# ESP_Robo_Board.net
KiCad netlist of a schematic drawn in EAGLE
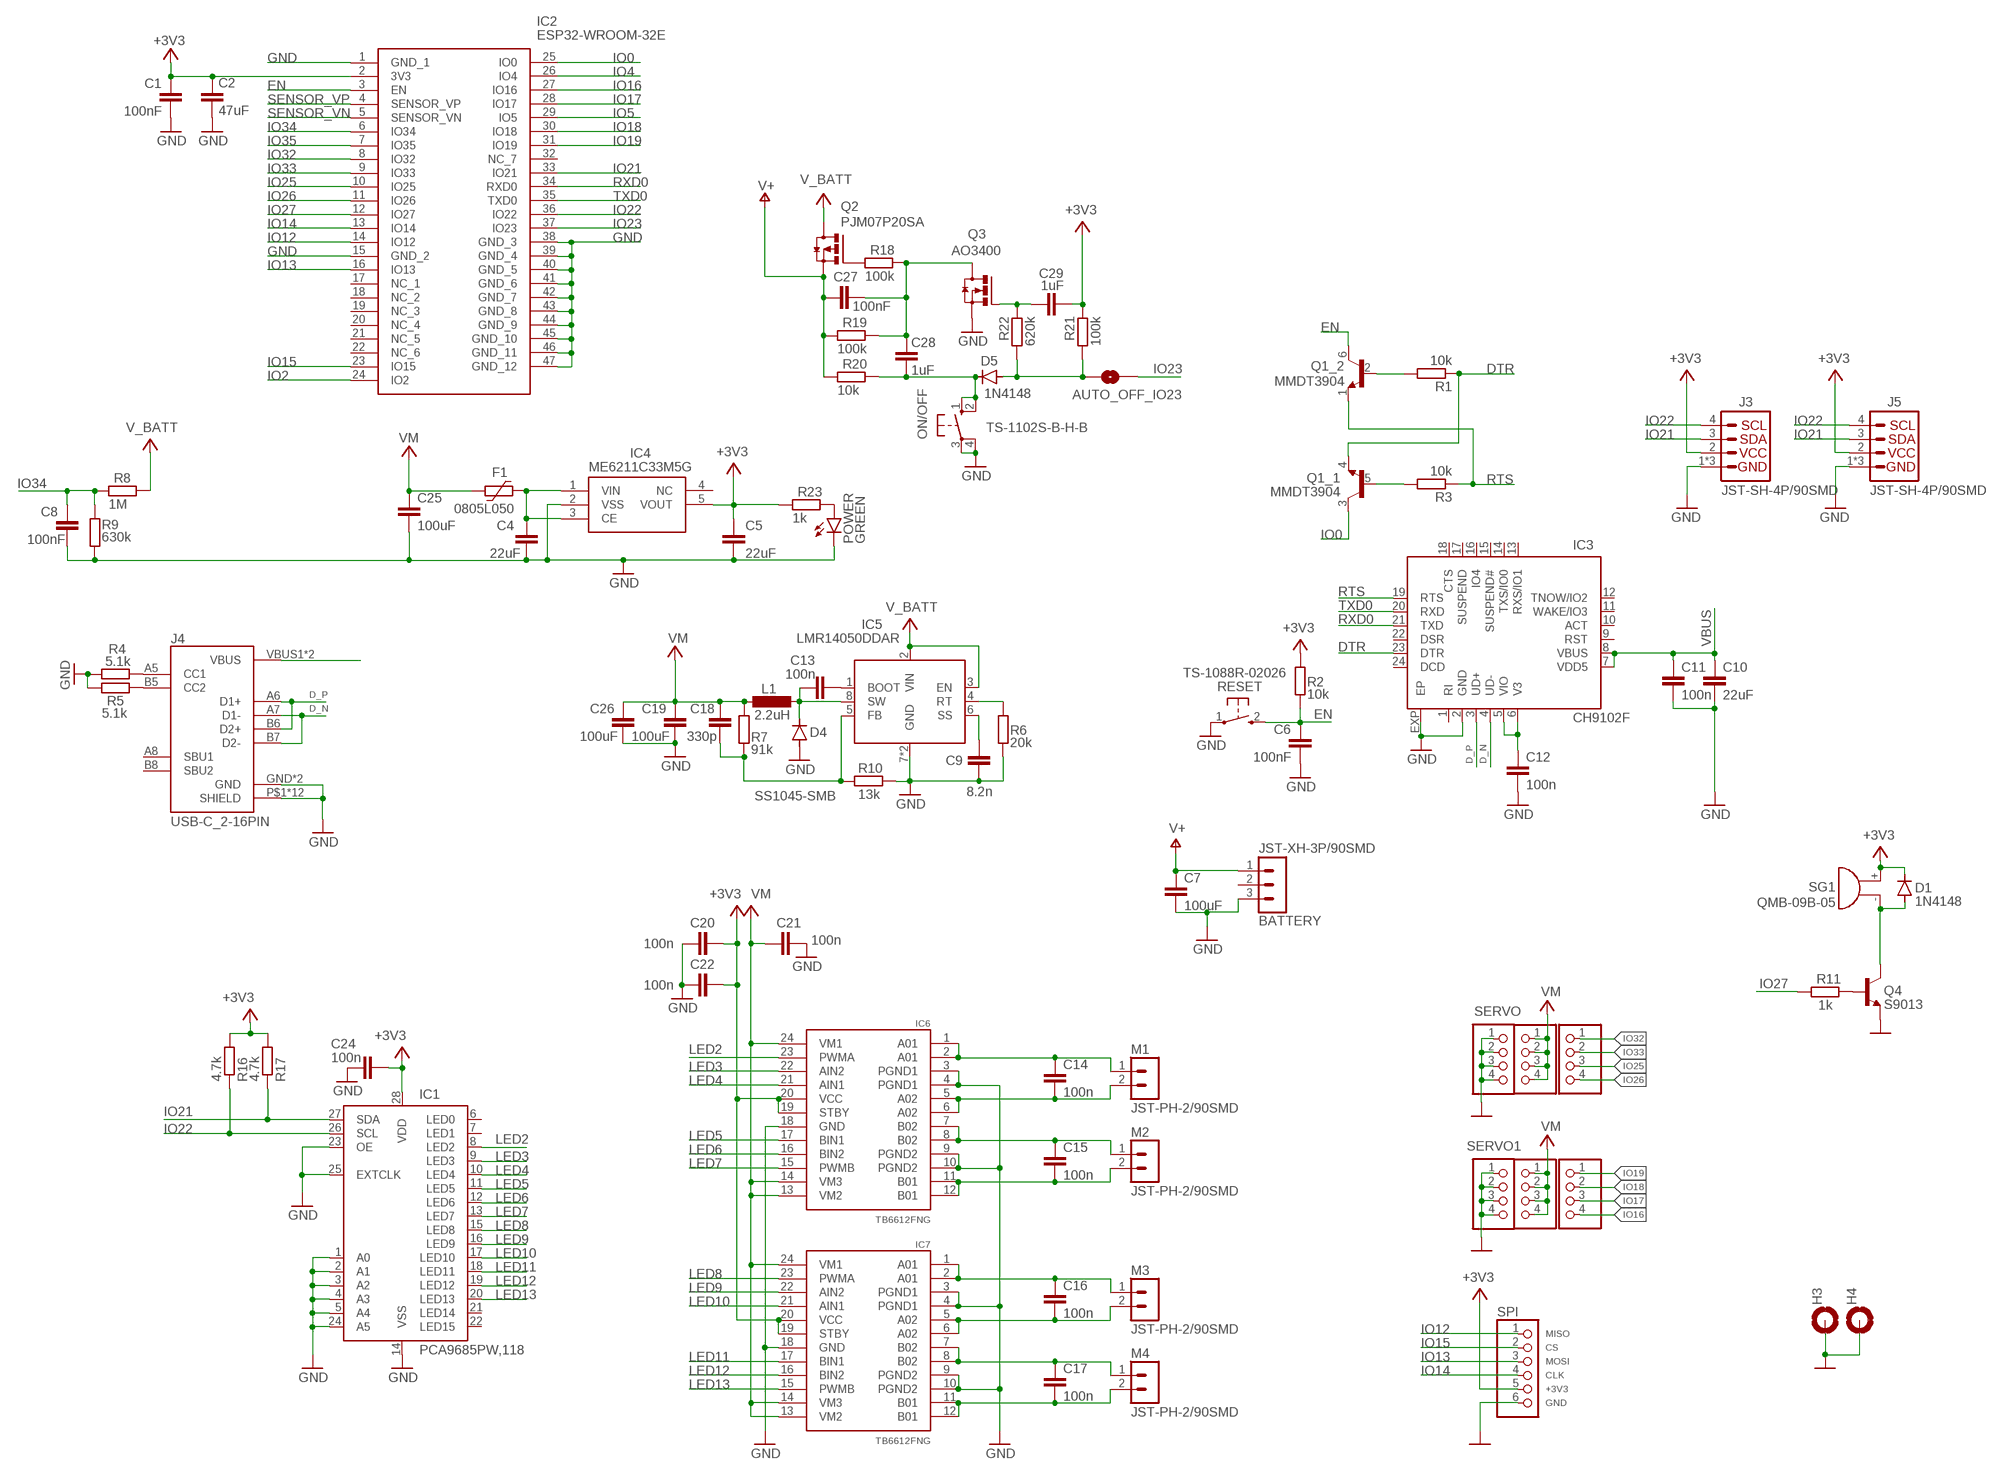
[diagram p0: schematic, sheet 1]

(export (version "E")
  (design (tool "Eeschema 10.0.6"))
  (components
    (comp (ref "1")
      (value "PINHD_1X4_RED")
      (footprint "eagle-import:1X04")
      (libsource (lib "eagle-import") (part "PINHD-1X4"))
    )
    (comp (ref "2")
      (value "PINHD_1X4_BLACK")
      (footprint "eagle-import:1X04")
      (libsource (lib "eagle-import") (part "PINHD-1X4"))
    )
    (comp (ref "5")
      (value "PINHD_1X4_RED")
      (footprint "eagle-import:1X04")
      (libsource (lib "eagle-import") (part "PINHD-1X4"))
    )
    (comp (ref "6")
      (value "PINHD_1X4_BLACK")
      (footprint "eagle-import:1X04")
      (libsource (lib "eagle-import") (part "PINHD-1X4"))
    )
    (comp (ref "AUTO_OFF_IO23")
      (value "nv")
      (footprint "eagle-import:SMT-JUMPER_2_NO_SILK")
      (libsource (lib "eagle-import") (part "JUMPER-SMT_2_NO_SILK"))
    )
    (comp (ref "BATTERY")
      (value "JST-XH-3P/90SMD")
      (footprint "eagle-import:S3B-XH-SM4")
      (libsource (lib "eagle-import") (part "JST-XH-3/90SMD"))
    )
    (comp (ref "C1")
      (value "100nF")
      (footprint "eagle-import:C0603")
      (libsource (lib "eagle-import") (part "C-EUC0603"))
    )
    (comp (ref "C2")
      (value "47uF")
      (footprint "eagle-import:C0805")
      (libsource (lib "eagle-import") (part "C-EUC0805"))
    )
    (comp (ref "C4")
      (value "22uF")
      (footprint "eagle-import:C0603")
      (libsource (lib "eagle-import") (part "C-EUC0603"))
    )
    (comp (ref "C5")
      (value "22uF")
      (footprint "eagle-import:C0603")
      (fields (field (name "LCSC_PART") "C19666"))
      (libsource (lib "eagle-import") (part "C-EUC0603"))
    )
    (comp (ref "C6")
      (value "100nF")
      (footprint "eagle-import:C0402")
      (libsource (lib "eagle-import") (part "CAPACITOR_0402"))
    )
    (comp (ref "C7")
      (value "100uF")
      (footprint "eagle-import:C1206")
      (libsource (lib "eagle-import") (part "C-EUC1206"))
    )
    (comp (ref "C8")
      (value "100nF")
      (footprint "eagle-import:C0402")
      (libsource (lib "eagle-import") (part "CAPACITOR_0402"))
    )
    (comp (ref "C9")
      (value "8.2n")
      (footprint "eagle-import:C0603")
      (libsource (lib "eagle-import") (part "C-EUC0603"))
    )
    (comp (ref "C10")
      (value "22uF")
      (footprint "eagle-import:C0603")
      (libsource (lib "eagle-import") (part "C-EUC0603"))
    )
    (comp (ref "C11")
      (value "100n")
      (footprint "eagle-import:C0402")
      (libsource (lib "eagle-import") (part "CAPACITOR_0402"))
    )
    (comp (ref "C12")
      (value "100n")
      (footprint "eagle-import:C0402")
      (libsource (lib "eagle-import") (part "CAPACITOR_0402"))
    )
    (comp (ref "C13")
      (value "100n")
      (footprint "eagle-import:C0603")
      (libsource (lib "eagle-import") (part "C-EUC0603"))
    )
    (comp (ref "C14")
      (value "100n")
      (footprint "eagle-import:C0603")
      (libsource (lib "eagle-import") (part "C-EUC0603"))
    )
    (comp (ref "C15")
      (value "100n")
      (footprint "eagle-import:C0603")
      (libsource (lib "eagle-import") (part "C-EUC0603"))
    )
    (comp (ref "C16")
      (value "100n")
      (footprint "eagle-import:C0603")
      (libsource (lib "eagle-import") (part "C-EUC0603"))
    )
    (comp (ref "C17")
      (value "100n")
      (footprint "eagle-import:C0603")
      (libsource (lib "eagle-import") (part "C-EUC0603"))
    )
    (comp (ref "C18")
      (value "330p")
      (footprint "eagle-import:C0402")
      (libsource (lib "eagle-import") (part "CAPACITOR_0402"))
    )
    (comp (ref "C19")
      (value "100uF")
      (footprint "eagle-import:C1206")
      (libsource (lib "eagle-import") (part "C-EUC1206"))
    )
    (comp (ref "C20")
      (value "100n")
      (footprint "eagle-import:C0603")
      (libsource (lib "eagle-import") (part "C-EUC0603"))
    )
    (comp (ref "C21")
      (value "100n")
      (footprint "eagle-import:C0603")
      (libsource (lib "eagle-import") (part "C-EUC0603"))
    )
    (comp (ref "C22")
      (value "100n")
      (footprint "eagle-import:C0603")
      (libsource (lib "eagle-import") (part "C-EUC0603"))
    )
    (comp (ref "C24")
      (value "100n")
      (footprint "eagle-import:C0603")
      (libsource (lib "eagle-import") (part "C-EUC0603"))
    )
    (comp (ref "C25")
      (value "100uF")
      (footprint "eagle-import:C1206")
      (libsource (lib "eagle-import") (part "C-EUC1206"))
    )
    (comp (ref "C26")
      (value "100uF")
      (footprint "eagle-import:C1206")
      (libsource (lib "eagle-import") (part "C-EUC1206"))
    )
    (comp (ref "C27")
      (value "100nF")
      (footprint "eagle-import:C0402")
      (libsource (lib "eagle-import") (part "CAPACITOR_0402"))
    )
    (comp (ref "C28")
      (value "1uF")
      (footprint "eagle-import:C0603")
      (libsource (lib "eagle-import") (part "C-EUC0603"))
    )
    (comp (ref "C29")
      (value "1uF")
      (footprint "eagle-import:C0603")
      (libsource (lib "eagle-import") (part "C-EUC0603"))
    )
    (comp (ref "D1")
      (value "1N4148")
      (footprint "eagle-import:SOD323-R")
      (fields (field (name "LCSC_PART") "C94001"))
      (libsource (lib "eagle-import") (part "diode_210_DIODE-SOD323-R"))
    )
    (comp (ref "D4")
      (value "SS1045-SMB")
      (footprint "eagle-import:SMB")
      (fields (field (name "LCSC_PART") "C2903947"))
      (libsource (lib "eagle-import") (part "DIODE-SMB"))
    )
    (comp (ref "D5")
      (value "1N4148")
      (footprint "eagle-import:SOD323-R")
      (libsource (lib "eagle-import") (part "DIODE-SOD323-R"))
    )
    (comp (ref "F1")
      (value "0805L050")
      (footprint "eagle-import:0805L")
      (fields (field (name "MF") "Littelfuse") (field (name "LCSC_PART") "C66452"))
      (libsource (lib "eagle-import") (part "?0805L050"))
    )
    (comp (ref "H3")
      (value "MOUNT-PAD-ROUND2.5")
      (footprint "eagle-import:2,5-PAD")
      (libsource (lib "eagle-import") (part "MOUNT-PAD-ROUND2.5"))
    )
    (comp (ref "H4")
      (value "MOUNT-PAD-ROUND2.5")
      (footprint "eagle-import:2,5-PAD")
      (libsource (lib "eagle-import") (part "MOUNT-PAD-ROUND2.5"))
    )
    (comp (ref "IC1")
      (value "PCA9685PW,118")
      (footprint "eagle-import:TSSOP28")
      (fields (field (name "LCSC_PART") "C2678753"))
      (libsource (lib "eagle-import") (part "PCA9685PW,118"))
    )
    (comp (ref "IC2")
      (value "ESP32-WROOM-32E")
      (footprint "eagle-import:ESP32WROOM32E")
      (libsource (lib "eagle-import") (part "ESP32-WROOM-32E"))
    )
    (comp (ref "IC3")
      (value "CH9102F")
      (footprint "eagle-import:QFN24-4X4")
      (libsource (lib "eagle-import") (part "USB_UART_CONVERTOR_CH9102"))
    )
    (comp (ref "IC4")
      (value "ME6211C33M5G")
      (footprint "eagle-import:SOT23-5")
      (libsource (lib "eagle-import") (part "LDO_ME6211C33M5G"))
    )
    (comp (ref "IC5")
      (value "LMR14050DDAR")
      (footprint "eagle-import:SO08-EPAD")
      (fields (field (name "LCSC_PART") "C155484"))
      (libsource (lib "eagle-import") (part "LMR14050DDAR"))
    )
    (comp (ref "IC6")
      (value "TB6612FNG")
      (footprint "eagle-import:SSOP24")
      (libsource (lib "eagle-import") (part "MOTOR_DRIVER_TB6612FNG"))
    )
    (comp (ref "IC7")
      (value "TB6612FNG")
      (footprint "eagle-import:SSOP24")
      (libsource (lib "eagle-import") (part "MOTOR_DRIVER_TB6612FNG"))
    )
    (comp (ref "J3")
      (value "JST-SH-4P/90SMD")
      (footprint "eagle-import:1X04_1MM_RA")
      (fields (field (name "LCSC_PART") "C145956"))
      (libsource (lib "eagle-import") (part "USUP_CONNECTOR_HOR"))
    )
    (comp (ref "J4")
      (value "USB-C_2-16PIN")
      (footprint "eagle-import:USBC_USB-C-16P-5")
      (fields (field (name "LCSC_PART") "C2837092"))
      (libsource (lib "eagle-import") (part "USB-C_2-16PIN"))
    )
    (comp (ref "J5")
      (value "JST-SH-4P/90SMD")
      (footprint "eagle-import:1X04_1MM_RA")
      (fields (field (name "LCSC_PART") "C145956"))
      (libsource (lib "eagle-import") (part "USUP_CONNECTOR_HOR"))
    )
    (comp (ref "L1")
      (value "2.2uH")
      (footprint "eagle-import:L5.4X5.2")
      (fields (field (name "LCSC_PART") "C351096"))
      (libsource (lib "eagle-import") (part "INDUCTOR_5.4X5.2"))
    )
    (comp (ref "M1")
      (value "JST-PH-2/90SMD")
      (footprint "eagle-import:S2B-PH-SM4")
      (fields (field (name "LCSC_PART") "C47647"))
      (libsource (lib "eagle-import") (part "JST-PH-2/90SMD"))
    )
    (comp (ref "M2")
      (value "JST-PH-2/90SMD")
      (footprint "eagle-import:S2B-PH-SM4")
      (fields (field (name "LCSC_PART") "C47647"))
      (libsource (lib "eagle-import") (part "JST-PH-2/90SMD"))
    )
    (comp (ref "M3")
      (value "JST-PH-2/90SMD")
      (footprint "eagle-import:S2B-PH-SM4")
      (fields (field (name "LCSC_PART") "C47647"))
      (libsource (lib "eagle-import") (part "JST-PH-2/90SMD"))
    )
    (comp (ref "M4")
      (value "JST-PH-2/90SMD")
      (footprint "eagle-import:S2B-PH-SM4")
      (fields (field (name "LCSC_PART") "C47647"))
      (libsource (lib "eagle-import") (part "JST-PH-2/90SMD"))
    )
    (comp (ref "ON/OFF")
      (value "TS-1102S-B-H-B")
      (footprint "eagle-import:B3F-SMD")
      (libsource (lib "eagle-import") (part "10-XX-SMD"))
    )
    (comp (ref "POWER")
      (value "GREEN")
      (footprint "eagle-import:CHIPLED_0402")
      (libsource (lib "eagle-import") (part "LEDCHIPLED_0402"))
    )
    (comp (ref "Q1")
      (value "MMDT3904")
      (footprint "eagle-import:SC70-6")
      (fields (field (name "LCSC_PART") "C268586"))
      (libsource (lib "eagle-import") (part "TRANS_NPN_DUAL-MBT3904DW1T1"))
    )
    (comp (ref "Q2")
      (value "PJM07P20SA")
      (footprint "eagle-import:SOT23")
      (fields (field (name "LCSC_PART") "C2856842"))
      (libsource (lib "eagle-import") (part "MOSFET_P-SOT-23"))
    )
    (comp (ref "Q3")
      (value "AO3400")
      (footprint "eagle-import:SOT23")
      (fields (field (name "LCSC_PART") "C693097"))
      (libsource (lib "eagle-import") (part "MOSFET_N-SOT-23"))
    )
    (comp (ref "Q4")
      (value "S9013")
      (footprint "eagle-import:SOT23-BEC")
      (fields (field (name "LCSC_PART") "C52801"))
      (libsource (lib "eagle-import") (part "-NPN-SOT23-BECBC817-16"))
    )
    (comp (ref "R1")
      (value "10k")
      (footprint "eagle-import:R0402")
      (libsource (lib "eagle-import") (part "R-EU_R0402"))
    )
    (comp (ref "R2")
      (value "10k")
      (footprint "eagle-import:R0402")
      (libsource (lib "eagle-import") (part "R-EU_R0402"))
    )
    (comp (ref "R3")
      (value "10k")
      (footprint "eagle-import:R0402")
      (libsource (lib "eagle-import") (part "R-EU_R0402"))
    )
    (comp (ref "R4")
      (value "5.1k")
      (footprint "eagle-import:R0402")
      (libsource (lib "eagle-import") (part "R-EU_R0402"))
    )
    (comp (ref "R5")
      (value "5.1k")
      (footprint "eagle-import:R0402")
      (libsource (lib "eagle-import") (part "R-EU_R0402"))
    )
    (comp (ref "R6")
      (value "20k")
      (footprint "eagle-import:R0402")
      (libsource (lib "eagle-import") (part "R-EU_R0402"))
    )
    (comp (ref "R7")
      (value "91k")
      (footprint "eagle-import:R0402")
      (libsource (lib "eagle-import") (part "R-EU_R0402"))
    )
    (comp (ref "R8")
      (value "1M")
      (footprint "eagle-import:R0402")
      (libsource (lib "eagle-import") (part "R-EU_R0402"))
    )
    (comp (ref "R9")
      (value "630k")
      (footprint "eagle-import:R0402")
      (libsource (lib "eagle-import") (part "R-EU_R0402"))
    )
    (comp (ref "R10")
      (value "13k")
      (footprint "eagle-import:R0402")
      (libsource (lib "eagle-import") (part "R-EU_R0402"))
    )
    (comp (ref "R11")
      (value "1k")
      (footprint "eagle-import:R0402")
      (fields (field (name "LCSC_PART") "C22548"))
      (libsource (lib "eagle-import") (part "R-EU_R0402"))
    )
    (comp (ref "R16")
      (value "4.7k")
      (footprint "eagle-import:R0402")
      (libsource (lib "eagle-import") (part "R-EU_R0402"))
    )
    (comp (ref "R17")
      (value "4.7k")
      (footprint "eagle-import:R0402")
      (libsource (lib "eagle-import") (part "R-EU_R0402"))
    )
    (comp (ref "R18")
      (value "100k")
      (footprint "eagle-import:R0402")
      (libsource (lib "eagle-import") (part "R-EU_R0402"))
    )
    (comp (ref "R19")
      (value "100k")
      (footprint "eagle-import:R0402")
      (libsource (lib "eagle-import") (part "R-EU_R0402"))
    )
    (comp (ref "R20")
      (value "10k")
      (footprint "eagle-import:R0402")
      (libsource (lib "eagle-import") (part "R-EU_R0402"))
    )
    (comp (ref "R21")
      (value "100k")
      (footprint "eagle-import:R0402")
      (libsource (lib "eagle-import") (part "R-EU_R0402"))
    )
    (comp (ref "R22")
      (value "620k")
      (footprint "eagle-import:R0402")
      (libsource (lib "eagle-import") (part "R-EU_R0402"))
    )
    (comp (ref "R23")
      (value "1k")
      (footprint "eagle-import:R0402")
      (libsource (lib "eagle-import") (part "R-EU_R0402"))
    )
    (comp (ref "RESET")
      (value "TS-1088R-02026")
      (footprint "eagle-import:TS1088R02026")
      (fields (field (name "LCSC_PART") "C455280"))
      (libsource (lib "eagle-import") (part "MOMENTARY_SWITCH_TS-1088R-02026"))
    )
    (comp (ref "SERVO")
      (value "PINHD_1X4_YELLOW")
      (footprint "eagle-import:1X04")
      (libsource (lib "eagle-import") (part "PINHD-1X4"))
    )
    (comp (ref "SERVO1")
      (value "PINHD_1X4_YELLOW")
      (footprint "eagle-import:1X04")
      (libsource (lib "eagle-import") (part "PINHD-1X4"))
    )
    (comp (ref "SG1")
      (value "QMB-09B-05")
      (footprint "eagle-import:9_4MM")
      (fields (field (name "LCSC_PART") "C161819"))
      (libsource (lib "eagle-import") (part "PASSIVE_5V_9/4MM"))
    )
    (comp (ref "SPI")
      (value "PINHD-1X6")
      (footprint "eagle-import:1X06")
      (libsource (lib "eagle-import") (part "PINHD-1X6"))
    )
  )
  (nets
    (net (code "1") (name "+3V3") (class "Default")
      (node (ref "C1") (pin "1") (pinfunction "1_1") (pintype "passive"))
      (node (ref "C2") (pin "1") (pinfunction "1_1") (pintype "passive"))
      (node (ref "C20") (pin "2") (pinfunction "2_2") (pintype "passive"))
      (node (ref "C22") (pin "2") (pinfunction "2_2") (pintype "passive"))
      (node (ref "C24") (pin "2") (pinfunction "2_2") (pintype "passive"))
      (node (ref "C29") (pin "1") (pinfunction "1_1") (pintype "passive"))
      (node (ref "C5") (pin "1") (pinfunction "1_1") (pintype "passive"))
      (node (ref "D1") (pin "C") (pinfunction "C_C") (pintype "passive"))
      (node (ref "IC1") (pin "28") (pinfunction "VDD_28") (pintype "bidirectional"))
      (node (ref "IC2") (pin "2") (pinfunction "3V3_2") (pintype "bidirectional"))
      (node (ref "IC4") (pin "5") (pinfunction "VOUT_5") (pintype "bidirectional"))
      (node (ref "IC6") (pin "19") (pinfunction "STBY_19") (pintype "bidirectional"))
      (node (ref "IC6") (pin "20") (pinfunction "VCC_20") (pintype "bidirectional"))
      (node (ref "IC7") (pin "19") (pinfunction "STBY_19") (pintype "bidirectional"))
      (node (ref "IC7") (pin "20") (pinfunction "VCC_20") (pintype "bidirectional"))
      (node (ref "J3") (pin "2") (pinfunction "VCC_2") (pintype "power_in"))
      (node (ref "J5") (pin "2") (pinfunction "VCC_2") (pintype "power_in"))
      (node (ref "R16") (pin "2") (pinfunction "2_2") (pintype "passive"))
      (node (ref "R17") (pin "2") (pinfunction "2_2") (pintype "passive"))
      (node (ref "R2") (pin "1") (pinfunction "1_1") (pintype "passive"))
      (node (ref "R21") (pin "2") (pinfunction "2_2") (pintype "passive"))
      (node (ref "R23") (pin "1") (pinfunction "1_1") (pintype "passive"))
      (node (ref "SG1") (pin "+") (pinfunction "+_+") (pintype "passive"))
      (node (ref "SPI") (pin "5") (pinfunction "5_5") (pintype "passive"))
    )
    (net (code "2") (name "/DTR") (class "Default")
      (node (ref "IC3") (pin "23") (pinfunction "DTR_23") (pintype "bidirectional"))
      (node (ref "Q1") (pin "4") (pinfunction "E_4") (pintype "passive"))
      (node (ref "R1") (pin "1") (pinfunction "1_1") (pintype "passive"))
    )
    (net (code "3") (name "/D_N") (class "Default")
      (node (ref "IC3") (pin "4") (pinfunction "UD-_4") (pintype "bidirectional"))
      (node (ref "J4") (pin "A7") (pinfunction "D1-_A7") (pintype "passive"))
      (node (ref "J4") (pin "B7") (pinfunction "D2-_B7") (pintype "passive"))
    )
    (net (code "4") (name "/D_P") (class "Default")
      (node (ref "IC3") (pin "3") (pinfunction "UD+_3") (pintype "bidirectional"))
      (node (ref "J4") (pin "A6") (pinfunction "D1+_A6") (pintype "passive"))
      (node (ref "J4") (pin "B6") (pinfunction "D2+_B6") (pintype "passive"))
    )
    (net (code "5") (name "/EN") (class "Default")
      (node (ref "C6") (pin "1") (pinfunction "1_1") (pintype "passive"))
      (node (ref "IC2") (pin "3") (pinfunction "EN_3") (pintype "bidirectional"))
      (node (ref "Q1") (pin "6") (pinfunction "C_6") (pintype "passive"))
      (node (ref "R2") (pin "2") (pinfunction "2_2") (pintype "passive"))
      (node (ref "RESET") (pin "2") (pinfunction "3_2") (pintype "passive"))
    )
    (net (code "6") (name "/IO0") (class "Default")
      (node (ref "IC2") (pin "25") (pinfunction "IO0_25") (pintype "bidirectional"))
      (node (ref "Q1") (pin "3") (pinfunction "C_3") (pintype "passive"))
    )
    (net (code "7") (name "/IO2") (class "Default")
      (node (ref "IC2") (pin "24") (pinfunction "IO2_24") (pintype "bidirectional"))
    )
    (net (code "8") (name "/IO4") (class "Default")
      (node (ref "IC2") (pin "26") (pinfunction "IO4_26") (pintype "bidirectional"))
    )
    (net (code "9") (name "/IO5") (class "Default")
      (node (ref "IC2") (pin "29") (pinfunction "IO5_29") (pintype "bidirectional"))
    )
    (net (code "10") (name "/IO12") (class "Default")
      (node (ref "IC2") (pin "14") (pinfunction "IO12_14") (pintype "bidirectional"))
      (node (ref "SPI") (pin "1") (pinfunction "1_1") (pintype "passive"))
    )
    (net (code "11") (name "/IO13") (class "Default")
      (node (ref "IC2") (pin "16") (pinfunction "IO13_16") (pintype "bidirectional"))
      (node (ref "SPI") (pin "3") (pinfunction "3_3") (pintype "passive"))
    )
    (net (code "12") (name "/IO14") (class "Default")
      (node (ref "IC2") (pin "13") (pinfunction "IO14_13") (pintype "bidirectional"))
      (node (ref "SPI") (pin "4") (pinfunction "4_4") (pintype "passive"))
    )
    (net (code "13") (name "/IO15") (class "Default")
      (node (ref "IC2") (pin "23") (pinfunction "IO15_23") (pintype "bidirectional"))
      (node (ref "SPI") (pin "2") (pinfunction "2_2") (pintype "passive"))
    )
    (net (code "14") (name "/IO21") (class "Default")
      (node (ref "IC1") (pin "27") (pinfunction "SDA_27") (pintype "bidirectional"))
      (node (ref "IC2") (pin "33") (pinfunction "IO21_33") (pintype "bidirectional"))
      (node (ref "J3") (pin "3") (pinfunction "SDA_3") (pintype "passive"))
      (node (ref "J5") (pin "3") (pinfunction "SDA_3") (pintype "passive"))
      (node (ref "R17") (pin "1") (pinfunction "1_1") (pintype "passive"))
    )
    (net (code "15") (name "/IO22") (class "Default")
      (node (ref "IC1") (pin "26") (pinfunction "SCL_26") (pintype "bidirectional"))
      (node (ref "IC2") (pin "36") (pinfunction "IO22_36") (pintype "bidirectional"))
      (node (ref "J3") (pin "4") (pinfunction "SCL_4") (pintype "passive"))
      (node (ref "J5") (pin "4") (pinfunction "SCL_4") (pintype "passive"))
      (node (ref "R16") (pin "1") (pinfunction "1_1") (pintype "passive"))
    )
    (net (code "16") (name "/IO23") (class "Default")
      (node (ref "AUTO_OFF_IO23") (pin "2") (pinfunction "2_2") (pintype "passive"))
      (node (ref "IC2") (pin "37") (pinfunction "IO23_37") (pintype "bidirectional"))
    )
    (net (code "17") (name "/IO27") (class "Default")
      (node (ref "IC2") (pin "12") (pinfunction "IO27_12") (pintype "bidirectional"))
      (node (ref "R11") (pin "1") (pinfunction "1_1") (pintype "passive"))
    )
    (net (code "18") (name "/IO34") (class "Default")
      (node (ref "C8") (pin "1") (pinfunction "1_1") (pintype "passive"))
      (node (ref "IC2") (pin "6") (pinfunction "IO34_6") (pintype "bidirectional"))
      (node (ref "R8") (pin "1") (pinfunction "1_1") (pintype "passive"))
      (node (ref "R9") (pin "2") (pinfunction "2_2") (pintype "passive"))
    )
    (net (code "19") (name "/IO35") (class "Default")
      (node (ref "IC2") (pin "7") (pinfunction "IO35_7") (pintype "bidirectional"))
    )
    (net (code "20") (name "/LED2") (class "Default")
      (node (ref "IC1") (pin "8") (pinfunction "LED2_8") (pintype "bidirectional"))
      (node (ref "IC6") (pin "23") (pinfunction "PWMA_23") (pintype "bidirectional"))
    )
    (net (code "21") (name "/LED3") (class "Default")
      (node (ref "IC1") (pin "9") (pinfunction "LED3_9") (pintype "bidirectional"))
      (node (ref "IC6") (pin "22") (pinfunction "AIN2_22") (pintype "bidirectional"))
    )
    (net (code "22") (name "/LED4") (class "Default")
      (node (ref "IC1") (pin "10") (pinfunction "LED4_10") (pintype "bidirectional"))
      (node (ref "IC6") (pin "21") (pinfunction "AIN1_21") (pintype "bidirectional"))
    )
    (net (code "23") (name "/LED5") (class "Default")
      (node (ref "IC1") (pin "11") (pinfunction "LED5_11") (pintype "bidirectional"))
      (node (ref "IC6") (pin "17") (pinfunction "BIN1_17") (pintype "bidirectional"))
    )
    (net (code "24") (name "/LED6") (class "Default")
      (node (ref "IC1") (pin "12") (pinfunction "LED6_12") (pintype "bidirectional"))
      (node (ref "IC6") (pin "16") (pinfunction "BIN2_16") (pintype "bidirectional"))
    )
    (net (code "25") (name "/LED7") (class "Default")
      (node (ref "IC1") (pin "13") (pinfunction "LED7_13") (pintype "bidirectional"))
      (node (ref "IC6") (pin "15") (pinfunction "PWMB_15") (pintype "bidirectional"))
    )
    (net (code "26") (name "/LED8") (class "Default")
      (node (ref "IC1") (pin "15") (pinfunction "LED8_15") (pintype "bidirectional"))
      (node (ref "IC7") (pin "23") (pinfunction "PWMA_23") (pintype "bidirectional"))
    )
    (net (code "27") (name "/LED9") (class "Default")
      (node (ref "IC1") (pin "16") (pinfunction "LED9_16") (pintype "bidirectional"))
      (node (ref "IC7") (pin "22") (pinfunction "AIN2_22") (pintype "bidirectional"))
    )
    (net (code "28") (name "/LED10") (class "Default")
      (node (ref "IC1") (pin "17") (pinfunction "LED10_17") (pintype "bidirectional"))
      (node (ref "IC7") (pin "21") (pinfunction "AIN1_21") (pintype "bidirectional"))
    )
    (net (code "29") (name "/LED11") (class "Default")
      (node (ref "IC1") (pin "18") (pinfunction "LED11_18") (pintype "bidirectional"))
      (node (ref "IC7") (pin "17") (pinfunction "BIN1_17") (pintype "bidirectional"))
    )
    (net (code "30") (name "/LED12") (class "Default")
      (node (ref "IC1") (pin "19") (pinfunction "LED12_19") (pintype "bidirectional"))
      (node (ref "IC7") (pin "16") (pinfunction "BIN2_16") (pintype "bidirectional"))
    )
    (net (code "31") (name "/LED13") (class "Default")
      (node (ref "IC1") (pin "20") (pinfunction "LED13_20") (pintype "bidirectional"))
      (node (ref "IC7") (pin "15") (pinfunction "PWMB_15") (pintype "bidirectional"))
    )
    (net (code "32") (name "/RTS") (class "Default")
      (node (ref "IC3") (pin "19") (pinfunction "RTS_19") (pintype "bidirectional"))
      (node (ref "Q1") (pin "1") (pinfunction "E_1") (pintype "passive"))
      (node (ref "R3") (pin "1") (pinfunction "1_1") (pintype "passive"))
    )
    (net (code "33") (name "/RXD0") (class "Default")
      (node (ref "IC2") (pin "34") (pinfunction "RXD0_34") (pintype "bidirectional"))
      (node (ref "IC3") (pin "21") (pinfunction "TXD_21") (pintype "bidirectional"))
    )
    (net (code "34") (name "/SENSOR_VN") (class "Default")
      (node (ref "IC2") (pin "5") (pinfunction "SENSOR_VN_5") (pintype "bidirectional"))
    )
    (net (code "35") (name "/SENSOR_VP") (class "Default")
      (node (ref "IC2") (pin "4") (pinfunction "SENSOR_VP_4") (pintype "bidirectional"))
    )
    (net (code "36") (name "/TXD0") (class "Default")
      (node (ref "IC2") (pin "35") (pinfunction "TXD0_35") (pintype "bidirectional"))
      (node (ref "IC3") (pin "20") (pinfunction "RXD_20") (pintype "bidirectional"))
    )
    (net (code "37") (name "/VBUS") (class "Default")
      (node (ref "C10") (pin "1") (pinfunction "1_1") (pintype "passive"))
      (node (ref "C11") (pin "1") (pinfunction "1_1") (pintype "passive"))
      (node (ref "IC3") (pin "7") (pinfunction "VDD5_7") (pintype "bidirectional"))
      (node (ref "IC3") (pin "8") (pinfunction "VBUS_8") (pintype "bidirectional"))
      (node (ref "J4") (pin "VBUS1") (pinfunction "VBUS_VBUS1") (pintype "passive"))
      (node (ref "J4") (pin "VBUS2") (pinfunction "VBUS_VBUS2") (pintype "passive"))
    )
    (net (code "38") (name "GND") (class "Default")
      (node (ref "2") (pin "1") (pinfunction "1_1") (pintype "passive"))
      (node (ref "2") (pin "2") (pinfunction "2_2") (pintype "passive"))
      (node (ref "2") (pin "3") (pinfunction "3_3") (pintype "passive"))
      (node (ref "2") (pin "4") (pinfunction "4_4") (pintype "passive"))
      (node (ref "6") (pin "1") (pinfunction "1_1") (pintype "passive"))
      (node (ref "6") (pin "2") (pinfunction "2_2") (pintype "passive"))
      (node (ref "6") (pin "3") (pinfunction "3_3") (pintype "passive"))
      (node (ref "6") (pin "4") (pinfunction "4_4") (pintype "passive"))
      (node (ref "BATTERY") (pin "3") (pinfunction "1_3") (pintype "passive"))
      (node (ref "C1") (pin "2") (pinfunction "2_2") (pintype "passive"))
      (node (ref "C10") (pin "2") (pinfunction "2_2") (pintype "passive"))
      (node (ref "C11") (pin "2") (pinfunction "2_2") (pintype "passive"))
      (node (ref "C12") (pin "2") (pinfunction "2_2") (pintype "passive"))
      (node (ref "C19") (pin "2") (pinfunction "2_2") (pintype "passive"))
      (node (ref "C2") (pin "2") (pinfunction "2_2") (pintype "passive"))
      (node (ref "C20") (pin "1") (pinfunction "1_1") (pintype "passive"))
      (node (ref "C21") (pin "2") (pinfunction "2_2") (pintype "passive"))
      (node (ref "C22") (pin "1") (pinfunction "1_1") (pintype "passive"))
      (node (ref "C24") (pin "1") (pinfunction "1_1") (pintype "passive"))
      (node (ref "C25") (pin "2") (pinfunction "2_2") (pintype "passive"))
      (node (ref "C26") (pin "2") (pinfunction "2_2") (pintype "passive"))
      (node (ref "C4") (pin "2") (pinfunction "2_2") (pintype "passive"))
      (node (ref "C5") (pin "2") (pinfunction "2_2") (pintype "passive"))
      (node (ref "C6") (pin "2") (pinfunction "2_2") (pintype "passive"))
      (node (ref "C7") (pin "2") (pinfunction "2_2") (pintype "passive"))
      (node (ref "C8") (pin "2") (pinfunction "2_2") (pintype "passive"))
      (node (ref "C9") (pin "2") (pinfunction "2_2") (pintype "passive"))
      (node (ref "D4") (pin "A") (pinfunction "A_A") (pintype "passive"))
      (node (ref "H3") (pin "1") (pinfunction "MOUNT_1") (pintype "passive"))
      (node (ref "H4") (pin "1") (pinfunction "MOUNT_1") (pintype "passive"))
      (node (ref "IC1") (pin "1") (pinfunction "A0_1") (pintype "bidirectional"))
      (node (ref "IC1") (pin "14") (pinfunction "VSS_14") (pintype "bidirectional"))
      (node (ref "IC1") (pin "2") (pinfunction "A1_2") (pintype "bidirectional"))
      (node (ref "IC1") (pin "23") (pinfunction "OE_23") (pintype "bidirectional"))
      (node (ref "IC1") (pin "24") (pinfunction "A5_24") (pintype "bidirectional"))
      (node (ref "IC1") (pin "25") (pinfunction "EXTCLK_25") (pintype "bidirectional"))
      (node (ref "IC1") (pin "3") (pinfunction "A2_3") (pintype "bidirectional"))
      (node (ref "IC1") (pin "4") (pinfunction "A3_4") (pintype "bidirectional"))
      (node (ref "IC1") (pin "5") (pinfunction "A4_5") (pintype "bidirectional"))
      (node (ref "IC2") (pin "1") (pinfunction "GND_1_1") (pintype "bidirectional"))
      (node (ref "IC2") (pin "15") (pinfunction "GND_2_15") (pintype "bidirectional"))
      (node (ref "IC2") (pin "38") (pinfunction "GND_3_38") (pintype "bidirectional"))
      (node (ref "IC2") (pin "39") (pinfunction "GND_4_39") (pintype "bidirectional"))
      (node (ref "IC2") (pin "40") (pinfunction "GND_5_40") (pintype "bidirectional"))
      (node (ref "IC2") (pin "41") (pinfunction "GND_6_41") (pintype "bidirectional"))
      (node (ref "IC2") (pin "42") (pinfunction "GND_7_42") (pintype "bidirectional"))
      (node (ref "IC2") (pin "43") (pinfunction "GND_8_43") (pintype "bidirectional"))
      (node (ref "IC2") (pin "44") (pinfunction "GND_9_44") (pintype "bidirectional"))
      (node (ref "IC2") (pin "45") (pinfunction "GND_10_45") (pintype "bidirectional"))
      (node (ref "IC2") (pin "46") (pinfunction "GND_11_46") (pintype "bidirectional"))
      (node (ref "IC2") (pin "47") (pinfunction "GND_12_47") (pintype "bidirectional"))
      (node (ref "IC3") (pin "2") (pinfunction "GND_2") (pintype "bidirectional"))
      (node (ref "IC3") (pin "EXP") (pinfunction "EP_EXP") (pintype "bidirectional"))
      (node (ref "IC4") (pin "2") (pinfunction "VSS_2") (pintype "bidirectional"))
      (node (ref "IC5") (pin "7") (pinfunction "GND_7") (pintype "bidirectional"))
      (node (ref "IC5") (pin "EPAD") (pinfunction "GND_EPAD") (pintype "bidirectional"))
      (node (ref "IC6") (pin "10") (pinfunction "PGND2_10") (pintype "bidirectional"))
      (node (ref "IC6") (pin "18") (pinfunction "GND_18") (pintype "bidirectional"))
      (node (ref "IC6") (pin "3") (pinfunction "PGND1_3") (pintype "bidirectional"))
      (node (ref "IC6") (pin "4") (pinfunction "PGND1_4") (pintype "bidirectional"))
      (node (ref "IC6") (pin "9") (pinfunction "PGND2_9") (pintype "bidirectional"))
      (node (ref "IC7") (pin "10") (pinfunction "PGND2_10") (pintype "bidirectional"))
      (node (ref "IC7") (pin "18") (pinfunction "GND_18") (pintype "bidirectional"))
      (node (ref "IC7") (pin "3") (pinfunction "PGND1_3") (pintype "bidirectional"))
      (node (ref "IC7") (pin "4") (pinfunction "PGND1_4") (pintype "bidirectional"))
      (node (ref "IC7") (pin "9") (pinfunction "PGND2_9") (pintype "bidirectional"))
      (node (ref "J3") (pin "1") (pinfunction "GND_1") (pintype "power_in"))
      (node (ref "J3") (pin "NC1") (pinfunction "GND_NC1") (pintype "power_in"))
      (node (ref "J3") (pin "NC2") (pinfunction "GND_NC2") (pintype "power_in"))
      (node (ref "J4") (pin "GND") (pinfunction "GND_GND") (pintype "passive"))
      (node (ref "J4") (pin "GND2") (pinfunction "GND_GND2") (pintype "passive"))
      (node (ref "J4") (pin "P$1") (pinfunction "SHIELD_P$1") (pintype "passive"))
      (node (ref "J4") (pin "P$2") (pinfunction "SHIELD_P$2") (pintype "passive"))
      (node (ref "J4") (pin "P$3") (pinfunction "SHIELD_P$3") (pintype "passive"))
      (node (ref "J4") (pin "P$4") (pinfunction "SHIELD_P$4") (pintype "passive"))
      (node (ref "J4") (pin "SHLD1") (pinfunction "SHIELD_SHLD1") (pintype "passive"))
      (node (ref "J4") (pin "SHLD2") (pinfunction "SHIELD_SHLD2") (pintype "passive"))
      (node (ref "J4") (pin "SHLD3") (pinfunction "SHIELD_SHLD3") (pintype "passive"))
      (node (ref "J4") (pin "SHLD4") (pinfunction "SHIELD_SHLD4") (pintype "passive"))
      (node (ref "J4") (pin "SHLD5") (pinfunction "SHIELD_SHLD5") (pintype "passive"))
      (node (ref "J4") (pin "SHLD6") (pinfunction "SHIELD_SHLD6") (pintype "passive"))
      (node (ref "J4") (pin "SHLD7") (pinfunction "SHIELD_SHLD7") (pintype "passive"))
      (node (ref "J4") (pin "SHLD8") (pinfunction "SHIELD_SHLD8") (pintype "passive"))
      (node (ref "J5") (pin "1") (pinfunction "GND_1") (pintype "power_in"))
      (node (ref "J5") (pin "NC1") (pinfunction "GND_NC1") (pintype "power_in"))
      (node (ref "J5") (pin "NC2") (pinfunction "GND_NC2") (pintype "power_in"))
      (node (ref "ON/OFF") (pin "3") (pinfunction "P_3") (pintype "passive"))
      (node (ref "ON/OFF") (pin "4") (pinfunction "P1_4") (pintype "passive"))
      (node (ref "POWER") (pin "C") (pinfunction "C_C") (pintype "passive"))
      (node (ref "Q3") (pin "2") (pinfunction "S_2") (pintype "passive"))
      (node (ref "Q4") (pin "E") (pinfunction "E_E") (pintype "passive"))
      (node (ref "R10") (pin "2") (pinfunction "2_2") (pintype "passive"))
      (node (ref "R4") (pin "1") (pinfunction "1_1") (pintype "passive"))
      (node (ref "R5") (pin "1") (pinfunction "1_1") (pintype "passive"))
      (node (ref "R6") (pin "2") (pinfunction "2_2") (pintype "passive"))
      (node (ref "R9") (pin "1") (pinfunction "1_1") (pintype "passive"))
      (node (ref "RESET") (pin "1") (pinfunction "1_1") (pintype "passive"))
      (node (ref "SPI") (pin "6") (pinfunction "6_6") (pintype "passive"))
    )
    (net (code "39") (name "IO16") (class "Default")
      (node (ref "IC2") (pin "27") (pinfunction "IO16_27") (pintype "bidirectional"))
      (node (ref "SERVO1") (pin "4") (pinfunction "4_4") (pintype "passive"))
    )
    (net (code "40") (name "IO17") (class "Default")
      (node (ref "IC2") (pin "28") (pinfunction "IO17_28") (pintype "bidirectional"))
      (node (ref "SERVO1") (pin "3") (pinfunction "3_3") (pintype "passive"))
    )
    (net (code "41") (name "IO18") (class "Default")
      (node (ref "IC2") (pin "30") (pinfunction "IO18_30") (pintype "bidirectional"))
      (node (ref "SERVO1") (pin "2") (pinfunction "2_2") (pintype "passive"))
    )
    (net (code "42") (name "IO19") (class "Default")
      (node (ref "IC2") (pin "31") (pinfunction "IO19_31") (pintype "bidirectional"))
      (node (ref "SERVO1") (pin "1") (pinfunction "1_1") (pintype "passive"))
    )
    (net (code "43") (name "IO25") (class "Default")
      (node (ref "IC2") (pin "10") (pinfunction "IO25_10") (pintype "bidirectional"))
      (node (ref "SERVO") (pin "3") (pinfunction "3_3") (pintype "passive"))
    )
    (net (code "44") (name "IO26") (class "Default")
      (node (ref "IC2") (pin "11") (pinfunction "IO26_11") (pintype "bidirectional"))
      (node (ref "SERVO") (pin "4") (pinfunction "4_4") (pintype "passive"))
    )
    (net (code "45") (name "IO32") (class "Default")
      (node (ref "IC2") (pin "8") (pinfunction "IO32_8") (pintype "bidirectional"))
      (node (ref "SERVO") (pin "1") (pinfunction "1_1") (pintype "passive"))
    )
    (net (code "46") (name "IO33") (class "Default")
      (node (ref "IC2") (pin "9") (pinfunction "IO33_9") (pintype "bidirectional"))
      (node (ref "SERVO") (pin "2") (pinfunction "2_2") (pintype "passive"))
    )
    (net (code "47") (name "Net-(AUTO_OFF_IO23-Pad1)") (class "Default")
      (node (ref "AUTO_OFF_IO23") (pin "1") (pinfunction "1_1") (pintype "passive"))
      (node (ref "D5") (pin "A") (pinfunction "A_A") (pintype "passive"))
      (node (ref "R21") (pin "1") (pinfunction "1_1") (pintype "passive"))
      (node (ref "R22") (pin "1") (pinfunction "1_1") (pintype "passive"))
    )
    (net (code "48") (name "Net-(C14-Pad1)") (class "Default")
      (node (ref "C14") (pin "1") (pinfunction "1_1") (pintype "passive"))
      (node (ref "IC6") (pin "1") (pinfunction "A01_1") (pintype "bidirectional"))
      (node (ref "IC6") (pin "2") (pinfunction "A01_2") (pintype "bidirectional"))
      (node (ref "M1") (pin "1") (pinfunction "1_1") (pintype "passive"))
    )
    (net (code "49") (name "Net-(C14-Pad2)") (class "Default")
      (node (ref "C14") (pin "2") (pinfunction "2_2") (pintype "passive"))
      (node (ref "IC6") (pin "5") (pinfunction "A02_5") (pintype "bidirectional"))
      (node (ref "IC6") (pin "6") (pinfunction "A02_6") (pintype "bidirectional"))
      (node (ref "M1") (pin "2") (pinfunction "2_2") (pintype "passive"))
    )
    (net (code "50") (name "Net-(C15-Pad1)") (class "Default")
      (node (ref "C15") (pin "1") (pinfunction "1_1") (pintype "passive"))
      (node (ref "IC6") (pin "7") (pinfunction "B02_7") (pintype "bidirectional"))
      (node (ref "IC6") (pin "8") (pinfunction "B02_8") (pintype "bidirectional"))
      (node (ref "M2") (pin "1") (pinfunction "1_1") (pintype "passive"))
    )
    (net (code "51") (name "Net-(C15-Pad2)") (class "Default")
      (node (ref "C15") (pin "2") (pinfunction "2_2") (pintype "passive"))
      (node (ref "IC6") (pin "11") (pinfunction "B01_11") (pintype "bidirectional"))
      (node (ref "IC6") (pin "12") (pinfunction "B01_12") (pintype "bidirectional"))
      (node (ref "M2") (pin "2") (pinfunction "2_2") (pintype "passive"))
    )
    (net (code "52") (name "Net-(C16-Pad1)") (class "Default")
      (node (ref "C16") (pin "1") (pinfunction "1_1") (pintype "passive"))
      (node (ref "IC7") (pin "1") (pinfunction "A01_1") (pintype "bidirectional"))
      (node (ref "IC7") (pin "2") (pinfunction "A01_2") (pintype "bidirectional"))
      (node (ref "M3") (pin "1") (pinfunction "1_1") (pintype "passive"))
    )
    (net (code "53") (name "Net-(C16-Pad2)") (class "Default")
      (node (ref "C16") (pin "2") (pinfunction "2_2") (pintype "passive"))
      (node (ref "IC7") (pin "5") (pinfunction "A02_5") (pintype "bidirectional"))
      (node (ref "IC7") (pin "6") (pinfunction "A02_6") (pintype "bidirectional"))
      (node (ref "M3") (pin "2") (pinfunction "2_2") (pintype "passive"))
    )
    (net (code "54") (name "Net-(C17-Pad1)") (class "Default")
      (node (ref "C17") (pin "1") (pinfunction "1_1") (pintype "passive"))
      (node (ref "IC7") (pin "7") (pinfunction "B02_7") (pintype "bidirectional"))
      (node (ref "IC7") (pin "8") (pinfunction "B02_8") (pintype "bidirectional"))
      (node (ref "M4") (pin "1") (pinfunction "1_1") (pintype "passive"))
    )
    (net (code "55") (name "Net-(C17-Pad2)") (class "Default")
      (node (ref "C17") (pin "2") (pinfunction "2_2") (pintype "passive"))
      (node (ref "IC7") (pin "11") (pinfunction "B01_11") (pintype "bidirectional"))
      (node (ref "IC7") (pin "12") (pinfunction "B01_12") (pintype "bidirectional"))
      (node (ref "M4") (pin "2") (pinfunction "2_2") (pintype "passive"))
    )
    (net (code "56") (name "Net-(D1-PadA)") (class "Default")
      (node (ref "D1") (pin "A") (pinfunction "A_A") (pintype "passive"))
      (node (ref "Q4") (pin "C") (pinfunction "C_C") (pintype "passive"))
      (node (ref "SG1") (pin "-") (pinfunction "-_-") (pintype "passive"))
    )
    (net (code "57") (name "Net-(IC3-V3)") (class "Default")
      (node (ref "C12") (pin "1") (pinfunction "1_1") (pintype "passive"))
      (node (ref "IC3") (pin "5") (pinfunction "VIO_5") (pintype "bidirectional"))
      (node (ref "IC3") (pin "6") (pinfunction "V3_6") (pintype "bidirectional"))
    )
    (net (code "58") (name "Net-(IC4-CE)") (class "Default")
      (node (ref "C4") (pin "1") (pinfunction "1_1") (pintype "passive"))
      (node (ref "F1") (pin "1") (pinfunction "1_1") (pintype "passive"))
      (node (ref "IC4") (pin "1") (pinfunction "VIN_1") (pintype "bidirectional"))
      (node (ref "IC4") (pin "3") (pinfunction "CE_3") (pintype "bidirectional"))
    )
    (net (code "59") (name "Net-(IC5-BOOT)") (class "Default")
      (node (ref "C13") (pin "2") (pinfunction "2_2") (pintype "passive"))
      (node (ref "IC5") (pin "1") (pinfunction "BOOT_1") (pintype "bidirectional"))
    )
    (net (code "60") (name "Net-(IC5-FB)") (class "Default")
      (node (ref "C18") (pin "2") (pinfunction "2_2") (pintype "passive"))
      (node (ref "IC5") (pin "5") (pinfunction "FB_5") (pintype "bidirectional"))
      (node (ref "R10") (pin "1") (pinfunction "1_1") (pintype "passive"))
      (node (ref "R7") (pin "2") (pinfunction "2_2") (pintype "passive"))
    )
    (net (code "61") (name "Net-(IC5-RT)") (class "Default")
      (node (ref "IC5") (pin "4") (pinfunction "RT_4") (pintype "bidirectional"))
      (node (ref "R6") (pin "1") (pinfunction "1_1") (pintype "passive"))
    )
    (net (code "62") (name "Net-(IC5-SS)") (class "Default")
      (node (ref "C9") (pin "1") (pinfunction "1_1") (pintype "passive"))
      (node (ref "IC5") (pin "6") (pinfunction "SS_6") (pintype "bidirectional"))
    )
    (net (code "63") (name "Net-(IC5-SW)") (class "Default")
      (node (ref "C13") (pin "1") (pinfunction "1_1") (pintype "passive"))
      (node (ref "D4") (pin "C") (pinfunction "C_C") (pintype "passive"))
      (node (ref "IC5") (pin "8") (pinfunction "SW_8") (pintype "bidirectional"))
      (node (ref "L1") (pin "1") (pinfunction "1_1") (pintype "passive"))
    )
    (net (code "64") (name "Net-(J4-CC1)") (class "Default")
      (node (ref "J4") (pin "A5") (pinfunction "CC1_A5") (pintype "passive"))
      (node (ref "R4") (pin "2") (pinfunction "2_2") (pintype "passive"))
    )
    (net (code "65") (name "Net-(J4-CC2)") (class "Default")
      (node (ref "J4") (pin "B5") (pinfunction "CC2_B5") (pintype "passive"))
      (node (ref "R5") (pin "2") (pinfunction "2_2") (pintype "passive"))
    )
    (net (code "66") (name "Net-(ON/OFF-S)") (class "Default")
      (node (ref "C28") (pin "2") (pinfunction "2_2") (pintype "passive"))
      (node (ref "D5") (pin "C") (pinfunction "C_C") (pintype "passive"))
      (node (ref "ON/OFF") (pin "1") (pinfunction "S_1") (pintype "passive"))
      (node (ref "ON/OFF") (pin "2") (pinfunction "S1_2") (pintype "passive"))
      (node (ref "R20") (pin "2") (pinfunction "2_2") (pintype "passive"))
    )
    (net (code "67") (name "Net-(POWER-PadA)") (class "Default")
      (node (ref "POWER") (pin "A") (pinfunction "A_A") (pintype "passive"))
      (node (ref "R23") (pin "2") (pinfunction "2_2") (pintype "passive"))
    )
    (net (code "68") (name "Net-(Q1A-B)") (class "Default")
      (node (ref "Q1") (pin "5") (pinfunction "B_5") (pintype "passive"))
      (node (ref "R3") (pin "2") (pinfunction "2_2") (pintype "passive"))
    )
    (net (code "69") (name "Net-(Q1B-B)") (class "Default")
      (node (ref "Q1") (pin "2") (pinfunction "B_2") (pintype "passive"))
      (node (ref "R1") (pin "2") (pinfunction "2_2") (pintype "passive"))
    )
    (net (code "70") (name "Net-(Q2-G)") (class "Default")
      (node (ref "Q2") (pin "1") (pinfunction "G_1") (pintype "passive"))
      (node (ref "R18") (pin "1") (pinfunction "1_1") (pintype "passive"))
    )
    (net (code "71") (name "Net-(Q3-D)") (class "Default")
      (node (ref "C27") (pin "2") (pinfunction "2_2") (pintype "passive"))
      (node (ref "C28") (pin "1") (pinfunction "1_1") (pintype "passive"))
      (node (ref "Q3") (pin "3") (pinfunction "D_3") (pintype "passive"))
      (node (ref "R18") (pin "2") (pinfunction "2_2") (pintype "passive"))
      (node (ref "R19") (pin "2") (pinfunction "2_2") (pintype "passive"))
    )
    (net (code "72") (name "Net-(Q3-G)") (class "Default")
      (node (ref "C29") (pin "2") (pinfunction "2_2") (pintype "passive"))
      (node (ref "Q3") (pin "1") (pinfunction "G_1") (pintype "passive"))
      (node (ref "R22") (pin "2") (pinfunction "2_2") (pintype "passive"))
    )
    (net (code "73") (name "Net-(Q4-PadB)") (class "Default")
      (node (ref "Q4") (pin "B") (pinfunction "B_B") (pintype "passive"))
      (node (ref "R11") (pin "2") (pinfunction "2_2") (pintype "passive"))
    )
    (net (code "74") (name "V+") (class "Default")
      (node (ref "BATTERY") (pin "1") (pinfunction "3_1") (pintype "passive"))
      (node (ref "C27") (pin "1") (pinfunction "1_1") (pintype "passive"))
      (node (ref "C7") (pin "1") (pinfunction "1_1") (pintype "passive"))
      (node (ref "Q2") (pin "2") (pinfunction "S_2") (pintype "passive"))
      (node (ref "R19") (pin "1") (pinfunction "1_1") (pintype "passive"))
      (node (ref "R20") (pin "1") (pinfunction "1_1") (pintype "passive"))
    )
    (net (code "75") (name "VM") (class "Default")
      (node (ref "1") (pin "1") (pinfunction "1_1") (pintype "passive"))
      (node (ref "1") (pin "2") (pinfunction "2_2") (pintype "passive"))
      (node (ref "1") (pin "3") (pinfunction "3_3") (pintype "passive"))
      (node (ref "1") (pin "4") (pinfunction "4_4") (pintype "passive"))
      (node (ref "5") (pin "1") (pinfunction "1_1") (pintype "passive"))
      (node (ref "5") (pin "2") (pinfunction "2_2") (pintype "passive"))
      (node (ref "5") (pin "3") (pinfunction "3_3") (pintype "passive"))
      (node (ref "5") (pin "4") (pinfunction "4_4") (pintype "passive"))
      (node (ref "C18") (pin "1") (pinfunction "1_1") (pintype "passive"))
      (node (ref "C19") (pin "1") (pinfunction "1_1") (pintype "passive"))
      (node (ref "C21") (pin "1") (pinfunction "1_1") (pintype "passive"))
      (node (ref "C25") (pin "1") (pinfunction "1_1") (pintype "passive"))
      (node (ref "C26") (pin "1") (pinfunction "1_1") (pintype "passive"))
      (node (ref "F1") (pin "2") (pinfunction "2_2") (pintype "passive"))
      (node (ref "IC6") (pin "13") (pinfunction "VM2_13") (pintype "bidirectional"))
      (node (ref "IC6") (pin "14") (pinfunction "VM3_14") (pintype "bidirectional"))
      (node (ref "IC6") (pin "24") (pinfunction "VM1_24") (pintype "bidirectional"))
      (node (ref "IC7") (pin "13") (pinfunction "VM2_13") (pintype "bidirectional"))
      (node (ref "IC7") (pin "14") (pinfunction "VM3_14") (pintype "bidirectional"))
      (node (ref "IC7") (pin "24") (pinfunction "VM1_24") (pintype "bidirectional"))
      (node (ref "L1") (pin "2") (pinfunction "2_2") (pintype "passive"))
      (node (ref "R7") (pin "1") (pinfunction "1_1") (pintype "passive"))
    )
    (net (code "76") (name "V_BATT") (class "Default")
      (node (ref "IC5") (pin "2") (pinfunction "VIN_2") (pintype "bidirectional"))
      (node (ref "IC5") (pin "3") (pinfunction "EN_3") (pintype "bidirectional"))
      (node (ref "Q2") (pin "3") (pinfunction "D_3") (pintype "passive"))
      (node (ref "R8") (pin "2") (pinfunction "2_2") (pintype "passive"))
    )
    (net (code "77") (name "unconnected-(BATTERY-Pad2)") (class "Default")
      (node (ref "BATTERY") (pin "2") (pinfunction "2_2") (pintype "passive"))
    )
    (net (code "78") (name "unconnected-(IC1-LED0-Pad6)") (class "Default")
      (node (ref "IC1") (pin "6") (pinfunction "LED0_6") (pintype "bidirectional"))
    )
    (net (code "79") (name "unconnected-(IC1-LED1-Pad7)") (class "Default")
      (node (ref "IC1") (pin "7") (pinfunction "LED1_7") (pintype "bidirectional"))
    )
    (net (code "80") (name "unconnected-(IC1-LED14-Pad21)") (class "Default")
      (node (ref "IC1") (pin "21") (pinfunction "LED14_21") (pintype "bidirectional"))
    )
    (net (code "81") (name "unconnected-(IC1-LED15-Pad22)") (class "Default")
      (node (ref "IC1") (pin "22") (pinfunction "LED15_22") (pintype "bidirectional"))
    )
    (net (code "82") (name "unconnected-(IC2-NC_1-Pad17)") (class "Default")
      (node (ref "IC2") (pin "17") (pinfunction "NC_1_17") (pintype "bidirectional"))
    )
    (net (code "83") (name "unconnected-(IC2-NC_2-Pad18)") (class "Default")
      (node (ref "IC2") (pin "18") (pinfunction "NC_2_18") (pintype "bidirectional"))
    )
    (net (code "84") (name "unconnected-(IC2-NC_3-Pad19)") (class "Default")
      (node (ref "IC2") (pin "19") (pinfunction "NC_3_19") (pintype "bidirectional"))
    )
    (net (code "85") (name "unconnected-(IC2-NC_4-Pad20)") (class "Default")
      (node (ref "IC2") (pin "20") (pinfunction "NC_4_20") (pintype "bidirectional"))
    )
    (net (code "86") (name "unconnected-(IC2-NC_5-Pad21)") (class "Default")
      (node (ref "IC2") (pin "21") (pinfunction "NC_5_21") (pintype "bidirectional"))
    )
    (net (code "87") (name "unconnected-(IC2-NC_6-Pad22)") (class "Default")
      (node (ref "IC2") (pin "22") (pinfunction "NC_6_22") (pintype "bidirectional"))
    )
    (net (code "88") (name "unconnected-(IC2-NC_7-Pad32)") (class "Default")
      (node (ref "IC2") (pin "32") (pinfunction "NC_7_32") (pintype "no_connect"))
    )
    (net (code "89") (name "unconnected-(IC3-ACT-Pad10)") (class "Default")
      (node (ref "IC3") (pin "10") (pinfunction "ACT_10") (pintype "bidirectional"))
    )
    (net (code "90") (name "unconnected-(IC3-CTS-Pad18)") (class "Default")
      (node (ref "IC3") (pin "18") (pinfunction "CTS_18") (pintype "bidirectional"))
    )
    (net (code "91") (name "unconnected-(IC3-DCD-Pad24)") (class "Default")
      (node (ref "IC3") (pin "24") (pinfunction "DCD_24") (pintype "bidirectional"))
    )
    (net (code "92") (name "unconnected-(IC3-DSR-Pad22)") (class "Default")
      (node (ref "IC3") (pin "22") (pinfunction "DSR_22") (pintype "bidirectional"))
    )
    (net (code "93") (name "unconnected-(IC3-IO4-Pad16)") (class "Default")
      (node (ref "IC3") (pin "16") (pinfunction "IO4_16") (pintype "bidirectional"))
    )
    (net (code "94") (name "unconnected-(IC3-RI-Pad1)") (class "Default")
      (node (ref "IC3") (pin "1") (pinfunction "RI_1") (pintype "bidirectional"))
    )
    (net (code "95") (name "unconnected-(IC3-RST-Pad9)") (class "Default")
      (node (ref "IC3") (pin "9") (pinfunction "RST_9") (pintype "bidirectional"))
    )
    (net (code "96") (name "unconnected-(IC3-RXS{slash}IO1-Pad13)") (class "Default")
      (node (ref "IC3") (pin "13") (pinfunction "RXS/IO1_13") (pintype "bidirectional"))
    )
    (net (code "97") (name "unconnected-(IC3-SUSPEND#-Pad15)") (class "Default")
      (node (ref "IC3") (pin "15") (pinfunction "SUSPEND#_15") (pintype "bidirectional"))
    )
    (net (code "98") (name "unconnected-(IC3-SUSPEND-Pad17)") (class "Default")
      (node (ref "IC3") (pin "17") (pinfunction "SUSPEND_17") (pintype "bidirectional"))
    )
    (net (code "99") (name "unconnected-(IC3-TNOW{slash}IO2-Pad12)") (class "Default")
      (node (ref "IC3") (pin "12") (pinfunction "TNOW/IO2_12") (pintype "bidirectional"))
    )
    (net (code "100") (name "unconnected-(IC3-TXS{slash}IO0-Pad14)") (class "Default")
      (node (ref "IC3") (pin "14") (pinfunction "TXS/IO0_14") (pintype "bidirectional"))
    )
    (net (code "101") (name "unconnected-(IC3-WAKE{slash}IO3-Pad11)") (class "Default")
      (node (ref "IC3") (pin "11") (pinfunction "WAKE/IO3_11") (pintype "bidirectional"))
    )
    (net (code "102") (name "unconnected-(IC4-NC-Pad4)") (class "Default")
      (node (ref "IC4") (pin "4") (pinfunction "NC_4") (pintype "no_connect"))
    )
    (net (code "103") (name "unconnected-(J4-SBU1-PadA8)") (class "Default")
      (node (ref "J4") (pin "A8") (pinfunction "SBU1_A8") (pintype "passive"))
    )
    (net (code "104") (name "unconnected-(J4-SBU2-PadB8)") (class "Default")
      (node (ref "J4") (pin "B8") (pinfunction "SBU2_B8") (pintype "passive"))
    )
  )
)
